# Power.net
KiCad netlist of a schematic drawn in Altium Designer
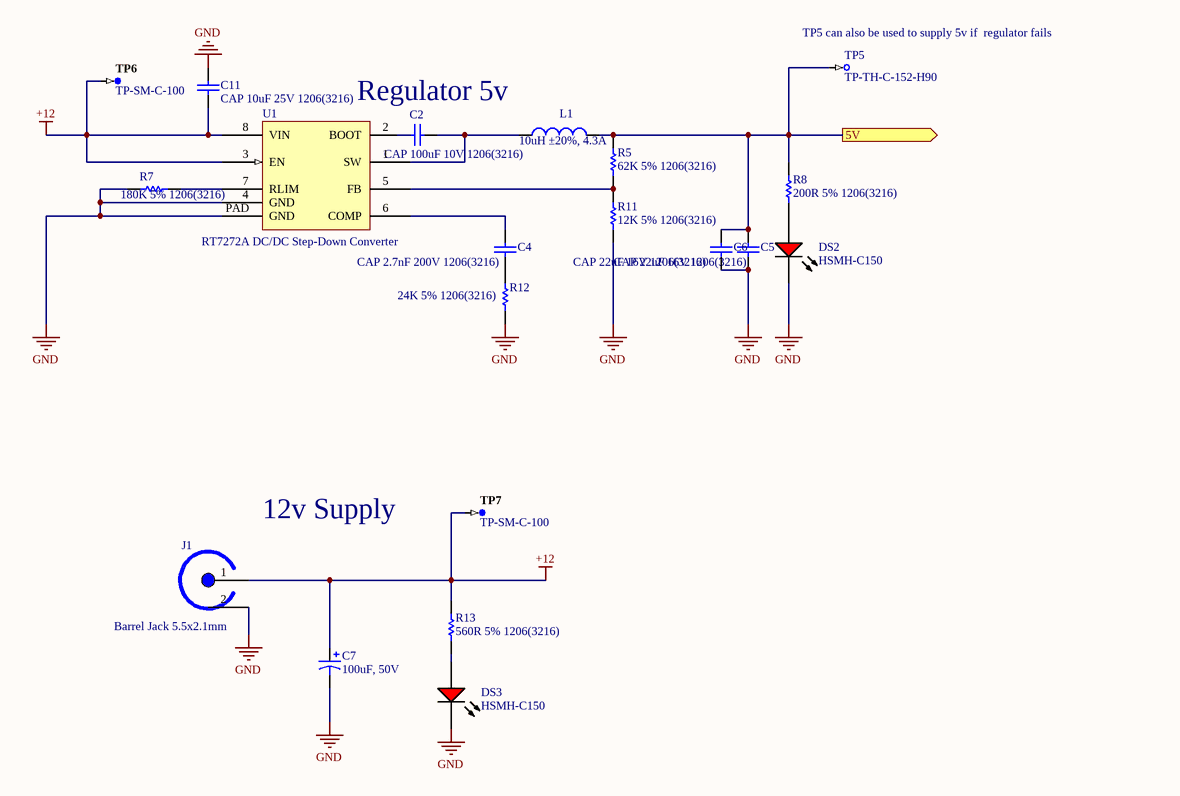
[diagram p0: Power.SchDoc]

(export (version "E")
  (design (tool "Eeschema 10.0.6"))
  (components
    (comp (ref "C2")
      (value "CAP 100uF 10V 1206(3216)")
      (footprint "CAPC1206(3216)190_L")
      (description "CAP 100uF 10V ±20% 1206 (3216 Metric) Thickness 1.9mm SMD")
      (fields (field (name "TOLERANCE") "Â±20%"))
      (libsource (lib "Altium Content Vault") (part "CAP"))
    )
    (comp (ref "C4")
      (value "CAP 2.7nF 200V 1206(3216)")
      (footprint "CAPC1206(3216)100_L")
      (description "CAP 2.7nF 200V ±5% 1206 (3216 Metric) Thickness 1mm SMD")
      (fields (field (name "TOLERANCE") "Â±5%"))
      (libsource (lib "Altium Content Vault") (part "CAP"))
    )
    (comp (ref "C5")
      (value "CAP 22uF 16V 1206(3216)")
      (footprint "CAPC1206(3216)190_N")
      (description "CAP 22uF 16V ±10% 1206 (3216 Metric) Thickness 1.9mm SMD")
      (fields (field (name "TOLERANCE") "Â±10%"))
      (libsource (lib "Altium Content Vault") (part "CAP"))
    )
    (comp (ref "C6")
      (value "CAP 22uF 16V 1206(3216)")
      (footprint "CAPC1206(3216)190_N")
      (description "CAP 22uF 16V ±10% 1206 (3216 Metric) Thickness 1.9mm SMD")
      (fields (field (name "TOLERANCE") "Â±10%"))
      (libsource (lib "Altium Content Vault") (part "CAP"))
    )
    (comp (ref "C7")
      (value "100uF, 50V")
      (footprint "Capacitor radial 8mm")
      (description "Electrolytic Capacitor, 100 µF, 50 V, ± 20%, Radial Leaded, 8 mm")
      (libsource (lib "JCULibrary_AS2 (1)") (part "Cap 100uF, 50V, THT radial"))
    )
    (comp (ref "C11")
      (value "CAP 10uF 25V 1206(3216)")
      (footprint "CAPC1206(3216)190_N")
      (description "CAP 10uF 25V ±20% 1206 (3216 Metric) Thickness 1.9mm SMD")
      (fields (field (name "TOLERANCE") "Â±20%"))
      (libsource (lib "Altium Content Vault") (part "CAP"))
    )
    (comp (ref "DS2")
      (value "HSMH-C150")
      (footprint "AVAG-HSMX-C150_V")
      (description "LED Uni-Color Red, 65 mW, 25 mA, -40 to 85 degC, 2-Pin SMD, RoHS, Tape and Reel")
      (fields (field (name "MANUFACTURER") "Avago"))
      (libsource (lib "Altium Content Vault") (part "LED-RED-AK-2"))
    )
    (comp (ref "DS3")
      (value "HSMH-C150")
      (footprint "AVAG-HSMX-C150_V")
      (description "LED Uni-Color Red, 65 mW, 25 mA, -40 to 85 degC, 2-Pin SMD, RoHS, Tape and Reel")
      (fields (field (name "MANUFACTURER") "Avago"))
      (libsource (lib "Altium Content Vault") (part "LED-RED-AK-2"))
    )
    (comp (ref "J1")
      (value "Barrel Jack 5.5x2.1mm")
      (footprint "Barrel Jack 2.1x5.5mm THT")
      (description "GCT DCJ200-10-A-K1-K")
      (libsource (lib "JCULibrary_AS2 (1)") (part "Barrel Jack 5.5x2.1mm"))
    )
    (comp (ref "L1")
      (value "10uH ±20%, 4.3A")
      (footprint "Inductor SMD VLF10045 series")
      (description "Inductor SMD - 10uH, 4.3A, ±20%")
      (libsource (lib "JCULibrary_AS2 (1)") (part "Inductor SMD VLF10045T-100M4R3 10uH"))
    )
    (comp (ref "R5")
      (value "62K 5% 1206(3216)")
      (footprint "RESC1206(3216)_M")
      (description "62K 0.25W 5% 1206 (3216 Metric)  SMD")
      (fields (field (name "TOLERANCE") "5 %") (field (name "POWER") "0.25 W"))
      (libsource (lib "Altium Content Vault") (part "RES"))
    )
    (comp (ref "R7")
      (value "180K 5% 1206(3216)")
      (footprint "RESC1206(3216)_N")
      (description "180K 0.25W 5% 1206 (3216 Metric)  SMD")
      (fields (field (name "POWER") "0.25 W") (field (name "TOLERANCE") "5 %"))
      (libsource (lib "Altium Content Vault") (part "RES"))
    )
    (comp (ref "R8")
      (value "200R 5% 1206(3216)")
      (footprint "RESC1206(3216)_L")
      (description "200R 0.25W 5% 1206 (3216 Metric)  SMD")
      (fields (field (name "TOLERANCE") "5 %") (field (name "POWER") "0.25 W"))
      (libsource (lib "Altium Content Vault") (part "RES"))
    )
    (comp (ref "R11")
      (value "12K 5% 1206(3216)")
      (footprint "RESC1206(3216)_N")
      (description "12K 0.25W 5% 1206 (3216 Metric)  SMD")
      (fields (field (name "POWER") "0.25 W") (field (name "TOLERANCE") "5 %"))
      (libsource (lib "Altium Content Vault") (part "RES"))
    )
    (comp (ref "R12")
      (value "24K 5% 1206(3216)")
      (footprint "RESC1206(3216)_M")
      (description "24K 0.25W 5% 1206 (3216 Metric)  SMD")
      (fields (field (name "POWER") "0.25 W") (field (name "TOLERANCE") "5 %"))
      (libsource (lib "Altium Content Vault") (part "RES"))
    )
    (comp (ref "R13")
      (value "560R 5% 1206(3216)")
      (footprint "RESC1206(3216)_L")
      (description "560R 0.25W 5% 1206 (3216 Metric)  SMD")
      (fields (field (name "TOLERANCE") "5 %") (field (name "POWER") "0.25 W"))
      (libsource (lib "Altium Content Vault") (part "RES"))
    )
    (comp (ref "TP5")
      (value "TP-TH-C-152-H90")
      (footprint "TP-TH-C-152-H90")
      (description "Test Point, Through Hole, Hole Size 0.9 mm, PCB Mount with Silkscreen Box")
      (fields (field (name "MANUFACTURER") "No Vendor"))
      (libsource (lib "Altium Content Vault") (part "TP-TH"))
    )
    (comp (ref "TP6")
      (value "TP-SM-C-100")
      (footprint "TP-SM-C-100")
      (description "Test Point, Surface Mount, Circular, Pad Diameter 1 mm")
      (fields (field (name "MANUFACTURER") "No Vendor"))
      (libsource (lib "Altium Content Vault") (part "TP-SM"))
    )
    (comp (ref "TP7")
      (value "TP-SM-C-100")
      (footprint "TP-SM-C-100")
      (description "Test Point, Surface Mount, Circular, Pad Diameter 1 mm")
      (fields (field (name "MANUFACTURER") "No Vendor"))
      (libsource (lib "Altium Content Vault") (part "TP-SM"))
    )
    (comp (ref "U1")
      (value "RT7272A DC/DC Step-Down Converter")
      (footprint "RT7272A")
      (description "RIchtek RT7272A 3A, 36V, 500kHz Synchronous Step-Down Converter")
      (libsource (lib "JCULibrary_AS2 (1)") (part "RT7272A DC/DC Step-Down Converter"))
    )
  )
  (nets
    (net (code "1") (name "+12") (class "Default")
      (node (ref "C11") (pin "1") (pinfunction "1_1") (pintype "passive"))
      (node (ref "C7") (pin "1") (pinfunction "1_1") (pintype "passive"))
      (node (ref "J1") (pin "1") (pinfunction "TIP_1") (pintype "power_in"))
      (node (ref "R13") (pin "1") (pinfunction "1_1") (pintype "passive"))
      (node (ref "TP6") (pin "1") (pinfunction "1_1") (pintype "input"))
      (node (ref "TP7") (pin "1") (pinfunction "1_1") (pintype "input"))
      (node (ref "U1") (pin "3") (pinfunction "EN_3") (pintype "input"))
      (node (ref "U1") (pin "8") (pinfunction "VIN_8") (pintype "power_in"))
    )
    (net (code "2") (name "/5V") (class "Default")
      (node (ref "C5") (pin "1") (pinfunction "1_1") (pintype "passive"))
      (node (ref "C6") (pin "1") (pinfunction "1_1") (pintype "passive"))
      (node (ref "L1") (pin "2") (pinfunction "2_2") (pintype "passive"))
      (node (ref "R5") (pin "2") (pinfunction "2_2") (pintype "passive"))
      (node (ref "R8") (pin "2") (pinfunction "2_2") (pintype "passive"))
      (node (ref "TP5") (pin "1") (pinfunction "1_1") (pintype "input"))
    )
    (net (code "3") (name "GND") (class "Default")
      (node (ref "C11") (pin "2") (pinfunction "2_2") (pintype "passive"))
      (node (ref "C5") (pin "2") (pinfunction "2_2") (pintype "passive"))
      (node (ref "C6") (pin "2") (pinfunction "2_2") (pintype "passive"))
      (node (ref "C7") (pin "2") (pinfunction "2_2") (pintype "passive"))
      (node (ref "DS2") (pin "2") (pinfunction "K_2") (pintype "passive"))
      (node (ref "DS3") (pin "2") (pinfunction "K_2") (pintype "passive"))
      (node (ref "J1") (pin "2") (pinfunction "SLEEVE_2") (pintype "power_in"))
      (node (ref "R11") (pin "1") (pinfunction "1_1") (pintype "passive"))
      (node (ref "R12") (pin "1") (pinfunction "1_1") (pintype "passive"))
      (node (ref "R7") (pin "2") (pinfunction "2_2") (pintype "passive"))
      (node (ref "U1") (pin "4") (pinfunction "GND_4") (pintype "power_in"))
      (node (ref "U1") (pin "PAD") (pinfunction "GND_PAD") (pintype "power_in"))
    )
    (net (code "4") (name "Net-(C4-Pad1)") (class "Default")
      (node (ref "C4") (pin "1") (pinfunction "1_1") (pintype "passive"))
      (node (ref "R12") (pin "2") (pinfunction "2_2") (pintype "passive"))
    )
    (net (code "5") (name "Net-(DS2-A)") (class "Default")
      (node (ref "DS2") (pin "1") (pinfunction "A_1") (pintype "passive"))
      (node (ref "R8") (pin "1") (pinfunction "1_1") (pintype "passive"))
    )
    (net (code "6") (name "Net-(DS3-A)") (class "Default")
      (node (ref "DS3") (pin "1") (pinfunction "A_1") (pintype "passive"))
      (node (ref "R13") (pin "2") (pinfunction "2_2") (pintype "passive"))
    )
    (net (code "7") (name "Net-(U1-BOOT)") (class "Default")
      (node (ref "C2") (pin "1") (pinfunction "1_1") (pintype "passive"))
      (node (ref "U1") (pin "2") (pinfunction "BOOT_2") (pintype "passive"))
    )
    (net (code "8") (name "Net-(U1-COMP)") (class "Default")
      (node (ref "C4") (pin "2") (pinfunction "2_2") (pintype "passive"))
      (node (ref "U1") (pin "6") (pinfunction "COMP_6") (pintype "passive"))
    )
    (net (code "9") (name "Net-(U1-FB)") (class "Default")
      (node (ref "R11") (pin "2") (pinfunction "2_2") (pintype "passive"))
      (node (ref "R5") (pin "1") (pinfunction "1_1") (pintype "passive"))
      (node (ref "U1") (pin "5") (pinfunction "FB_5") (pintype "passive"))
    )
    (net (code "10") (name "Net-(U1-RLIM)") (class "Default")
      (node (ref "R7") (pin "1") (pinfunction "1_1") (pintype "passive"))
      (node (ref "U1") (pin "7") (pinfunction "RLIM_7") (pintype "passive"))
    )
    (net (code "11") (name "Net-(U1-SW)") (class "Default")
      (node (ref "C2") (pin "2") (pinfunction "2_2") (pintype "passive"))
      (node (ref "L1") (pin "1") (pinfunction "1_1") (pintype "passive"))
      (node (ref "U1") (pin "1") (pinfunction "SW_1") (pintype "passive"))
    )
  )
)
